# cs301_Group15.net
KiCad netlist of a schematic drawn in Altium Designer
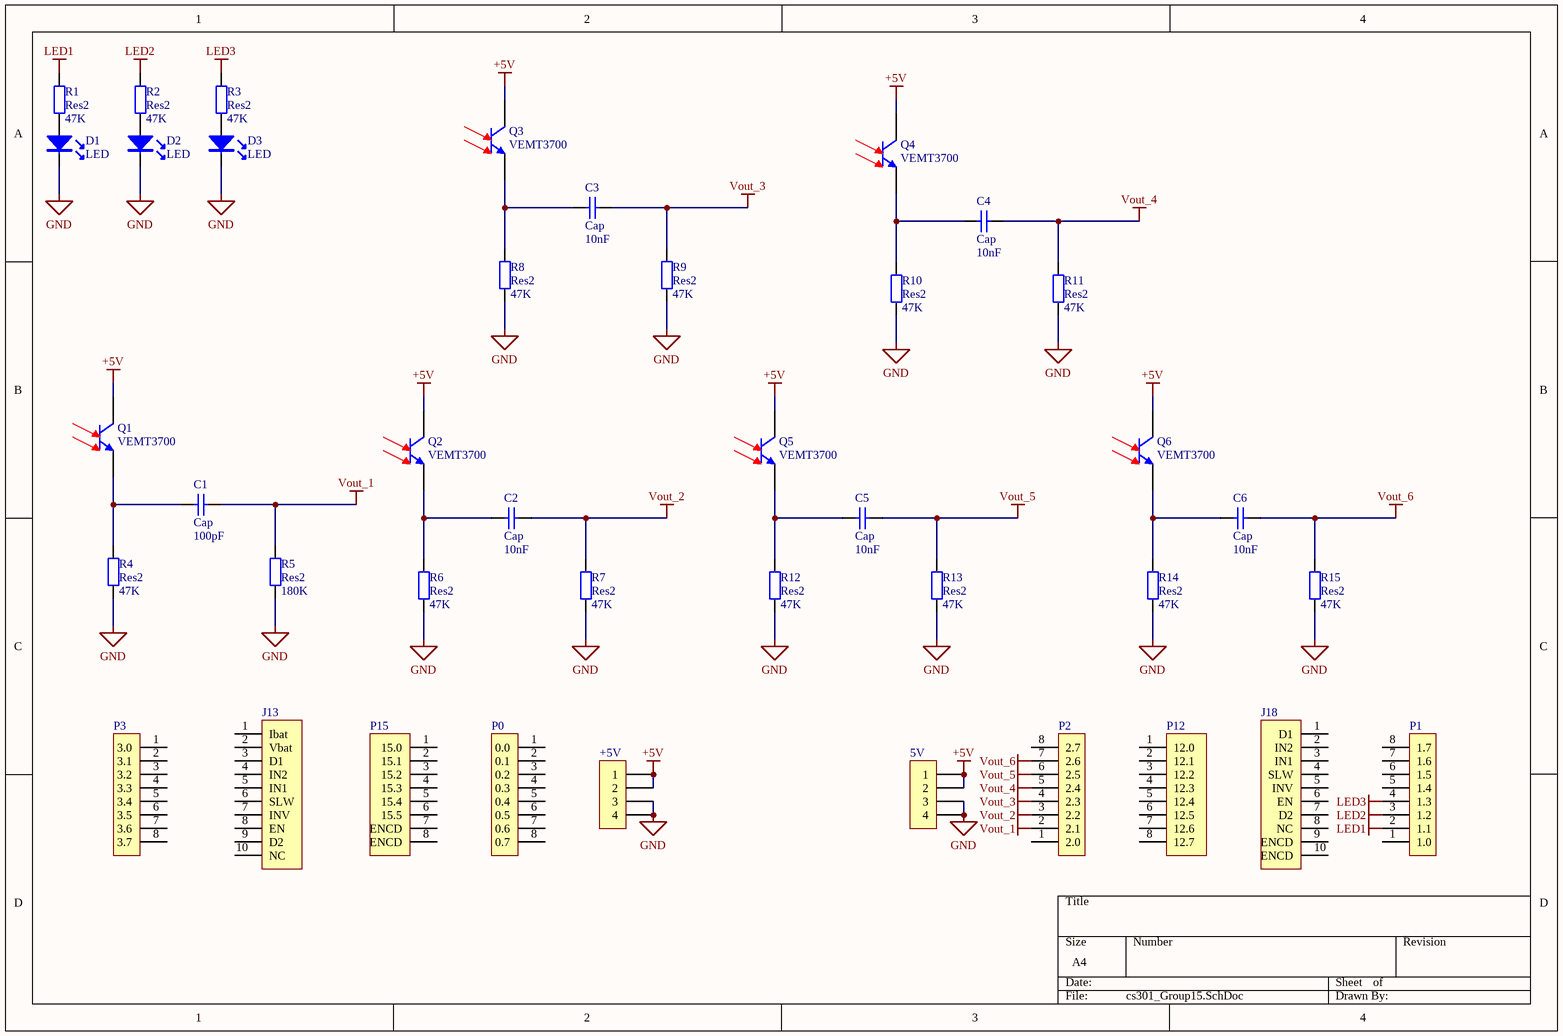
[diagram p0: cs301_Group15.SchDoc]

(export (version "E")
  (design (tool "Eeschema 10.0.6"))
  (components
    (comp (ref "+5V")
      (value "5V")
      (footprint "IDC4")
      (description "Connector")
      (libsource (lib "Miscellaneous Devices") (part "CON4"))
    )
    (comp (ref "5V")
      (value "5V")
      (footprint "IDC4")
      (description "Connector")
      (libsource (lib "Miscellaneous Devices") (part "CON4"))
    )
    (comp (ref "C1")
      (value "Cap")
      (footprint "RAD-0.3")
      (description "Capacitor")
      (fields (field (name "ALTIUM_VALUE") "100pF") (field (name "PUBLISHER") "Altium Limited"))
      (libsource (lib "Miscellaneous Devices") (part "Cap"))
    )
    (comp (ref "C2")
      (value "Cap")
      (footprint "RAD-0.3")
      (description "Capacitor")
      (fields (field (name "ALTIUM_VALUE") "10nF") (field (name "PUBLISHER") "Altium Limited"))
      (libsource (lib "Miscellaneous Devices") (part "Cap"))
    )
    (comp (ref "C3")
      (value "Cap")
      (footprint "RAD-0.3")
      (description "Capacitor")
      (fields (field (name "ALTIUM_VALUE") "10nF") (field (name "PUBLISHER") "Altium Limited"))
      (libsource (lib "Miscellaneous Devices") (part "Cap"))
    )
    (comp (ref "C4")
      (value "Cap")
      (footprint "RAD-0.3")
      (description "Capacitor")
      (fields (field (name "ALTIUM_VALUE") "10nF") (field (name "PUBLISHER") "Altium Limited"))
      (libsource (lib "Miscellaneous Devices") (part "Cap"))
    )
    (comp (ref "C5")
      (value "Cap")
      (footprint "RAD-0.3")
      (description "Capacitor")
      (fields (field (name "ALTIUM_VALUE") "10nF") (field (name "PUBLISHER") "Altium Limited"))
      (libsource (lib "Miscellaneous Devices") (part "Cap"))
    )
    (comp (ref "C6")
      (value "Cap")
      (footprint "RAD-0.3")
      (description "Capacitor")
      (fields (field (name "ALTIUM_VALUE") "10nF") (field (name "PUBLISHER") "Altium Limited"))
      (libsource (lib "Miscellaneous Devices") (part "Cap"))
    )
    (comp (ref "D1") (value "LED") (footprint "LED0.1/5MM") (libsource (lib "COMSYS301_2013") (part "LED")))
    (comp (ref "D2") (value "LED") (footprint "LED0.1/5MM") (libsource (lib "COMSYS301_2013") (part "LED")))
    (comp (ref "D3") (value "LED") (footprint "LED0.1/5MM") (libsource (lib "COMSYS301_2013") (part "LED")))
    (comp (ref "J13")
      (value "CON10")
      (footprint "idc10")
      (description "Connector")
      (libsource (lib "") (part "CON10_1"))
    )
    (comp (ref "J18")
      (value "CON10")
      (footprint "IDC10")
      (description "Connector")
      (libsource (lib "Miscellaneous Devices") (part "CON10"))
    )
    (comp (ref "P0")
      (value "P0")
      (footprint "idc8")
      (description "Connector")
      (libsource (lib "Miscellaneous Devices") (part "CON8"))
    )
    (comp (ref "P1")
      (value "P1")
      (footprint "idc8")
      (description "Connector")
      (libsource (lib "") (part "CON8_2"))
    )
    (comp (ref "P2")
      (value "P2")
      (footprint "idc8")
      (description "Connector")
      (libsource (lib "") (part "CON8_1"))
    )
    (comp (ref "P3")
      (value "P3")
      (footprint "idc8")
      (description "Connector")
      (libsource (lib "Miscellaneous Devices") (part "CON8"))
    )
    (comp (ref "P12")
      (value "P12")
      (footprint "idc8")
      (description "Connector")
      (libsource (lib "Miscellaneous Devices") (part "CON8_1"))
    )
    (comp (ref "P15")
      (value "P15")
      (footprint "idc8")
      (description "Connector")
      (libsource (lib "") (part "CON8_1_1"))
    )
    (comp (ref "Q1")
      (value "VEMT3700")
      (footprint "VEMT3700")
      (description "Silicon NPN Phototransistor")
      (libsource (lib "COMSYS301_2013") (part "VEMT3700"))
    )
    (comp (ref "Q2")
      (value "VEMT3700")
      (footprint "VEMT3700")
      (description "Silicon NPN Phototransistor")
      (libsource (lib "COMSYS301_2013") (part "VEMT3700"))
    )
    (comp (ref "Q3")
      (value "VEMT3700")
      (footprint "VEMT3700")
      (description "Silicon NPN Phototransistor")
      (libsource (lib "COMSYS301_2013") (part "VEMT3700"))
    )
    (comp (ref "Q4")
      (value "VEMT3700")
      (footprint "VEMT3700")
      (description "Silicon NPN Phototransistor")
      (libsource (lib "COMSYS301_2013") (part "VEMT3700"))
    )
    (comp (ref "Q5")
      (value "VEMT3700")
      (footprint "VEMT3700")
      (description "Silicon NPN Phototransistor")
      (libsource (lib "COMSYS301_2013") (part "VEMT3700"))
    )
    (comp (ref "Q6")
      (value "VEMT3700")
      (footprint "VEMT3700")
      (description "Silicon NPN Phototransistor")
      (libsource (lib "COMSYS301_2013") (part "VEMT3700"))
    )
    (comp (ref "R1")
      (value "Res2")
      (footprint "AXIAL-0.4")
      (description "Resistor")
      (fields (field (name "ALTIUM_VALUE") "47K") (field (name "PUBLISHER") "Altium Limited"))
      (libsource (lib "Miscellaneous Devices") (part "Res2"))
    )
    (comp (ref "R2")
      (value "Res2")
      (footprint "AXIAL-0.4")
      (description "Resistor")
      (fields (field (name "ALTIUM_VALUE") "47K") (field (name "PUBLISHER") "Altium Limited"))
      (libsource (lib "Miscellaneous Devices") (part "Res2"))
    )
    (comp (ref "R3")
      (value "Res2")
      (footprint "AXIAL-0.4")
      (description "Resistor")
      (fields (field (name "ALTIUM_VALUE") "47K") (field (name "PUBLISHER") "Altium Limited"))
      (libsource (lib "Miscellaneous Devices") (part "Res2"))
    )
    (comp (ref "R4")
      (value "Res2")
      (footprint "AXIAL-0.4")
      (description "Resistor")
      (fields (field (name "ALTIUM_VALUE") "47K") (field (name "PUBLISHER") "Altium Limited"))
      (libsource (lib "Miscellaneous Devices") (part "Res2"))
    )
    (comp (ref "R5")
      (value "Res2")
      (footprint "AXIAL-0.4")
      (description "Resistor")
      (fields (field (name "ALTIUM_VALUE") "180K") (field (name "PUBLISHER") "Altium Limited"))
      (libsource (lib "Miscellaneous Devices") (part "Res2"))
    )
    (comp (ref "R6")
      (value "Res2")
      (footprint "AXIAL-0.4")
      (description "Resistor")
      (fields (field (name "ALTIUM_VALUE") "47K") (field (name "PUBLISHER") "Altium Limited"))
      (libsource (lib "Miscellaneous Devices") (part "Res2"))
    )
    (comp (ref "R7")
      (value "Res2")
      (footprint "AXIAL-0.4")
      (description "Resistor")
      (fields (field (name "ALTIUM_VALUE") "47K") (field (name "PUBLISHER") "Altium Limited"))
      (libsource (lib "Miscellaneous Devices") (part "Res2"))
    )
    (comp (ref "R8")
      (value "Res2")
      (footprint "AXIAL-0.4")
      (description "Resistor")
      (fields (field (name "ALTIUM_VALUE") "47K") (field (name "PUBLISHER") "Altium Limited"))
      (libsource (lib "Miscellaneous Devices") (part "Res2"))
    )
    (comp (ref "R9")
      (value "Res2")
      (footprint "AXIAL-0.4")
      (description "Resistor")
      (fields (field (name "ALTIUM_VALUE") "47K") (field (name "PUBLISHER") "Altium Limited"))
      (libsource (lib "Miscellaneous Devices") (part "Res2"))
    )
    (comp (ref "R10")
      (value "Res2")
      (footprint "AXIAL-0.4")
      (description "Resistor")
      (fields (field (name "ALTIUM_VALUE") "47K") (field (name "PUBLISHER") "Altium Limited"))
      (libsource (lib "Miscellaneous Devices") (part "Res2"))
    )
    (comp (ref "R11")
      (value "Res2")
      (footprint "AXIAL-0.4")
      (description "Resistor")
      (fields (field (name "ALTIUM_VALUE") "47K") (field (name "PUBLISHER") "Altium Limited"))
      (libsource (lib "Miscellaneous Devices") (part "Res2"))
    )
    (comp (ref "R12")
      (value "Res2")
      (footprint "AXIAL-0.4")
      (description "Resistor")
      (fields (field (name "ALTIUM_VALUE") "47K") (field (name "PUBLISHER") "Altium Limited"))
      (libsource (lib "Miscellaneous Devices") (part "Res2"))
    )
    (comp (ref "R13")
      (value "Res2")
      (footprint "AXIAL-0.4")
      (description "Resistor")
      (fields (field (name "ALTIUM_VALUE") "47K") (field (name "PUBLISHER") "Altium Limited"))
      (libsource (lib "Miscellaneous Devices") (part "Res2"))
    )
    (comp (ref "R14")
      (value "Res2")
      (footprint "AXIAL-0.4")
      (description "Resistor")
      (fields (field (name "ALTIUM_VALUE") "47K") (field (name "PUBLISHER") "Altium Limited"))
      (libsource (lib "Miscellaneous Devices") (part "Res2"))
    )
    (comp (ref "R15")
      (value "Res2")
      (footprint "AXIAL-0.4")
      (description "Resistor")
      (fields (field (name "ALTIUM_VALUE") "47K") (field (name "PUBLISHER") "Altium Limited"))
      (libsource (lib "Miscellaneous Devices") (part "Res2"))
    )
  )
  (nets
    (net (code "1") (name "+5V") (class "Default")
      (node (ref "+5V") (pin "1") (pinfunction "1_1") (pintype "passive"))
      (node (ref "+5V") (pin "2") (pinfunction "2_2") (pintype "passive"))
      (node (ref "5V") (pin "1") (pinfunction "1_1") (pintype "passive"))
      (node (ref "5V") (pin "2") (pinfunction "2_2") (pintype "passive"))
      (node (ref "Q1") (pin "1") (pinfunction "C_1") (pintype "passive"))
      (node (ref "Q2") (pin "1") (pinfunction "C_1") (pintype "passive"))
      (node (ref "Q3") (pin "1") (pinfunction "C_1") (pintype "passive"))
      (node (ref "Q4") (pin "1") (pinfunction "C_1") (pintype "passive"))
      (node (ref "Q5") (pin "1") (pinfunction "C_1") (pintype "passive"))
      (node (ref "Q6") (pin "1") (pinfunction "C_1") (pintype "passive"))
    )
    (net (code "2") (name "GND") (class "Default")
      (node (ref "+5V") (pin "3") (pinfunction "3_3") (pintype "passive"))
      (node (ref "+5V") (pin "4") (pinfunction "4_4") (pintype "passive"))
      (node (ref "5V") (pin "3") (pinfunction "3_3") (pintype "passive"))
      (node (ref "5V") (pin "4") (pinfunction "4_4") (pintype "passive"))
      (node (ref "D1") (pin "K") (pinfunction "2_K") (pintype "passive"))
      (node (ref "D2") (pin "K") (pinfunction "2_K") (pintype "passive"))
      (node (ref "D3") (pin "K") (pinfunction "2_K") (pintype "passive"))
      (node (ref "R10") (pin "1") (pinfunction "1_1") (pintype "passive"))
      (node (ref "R11") (pin "1") (pinfunction "1_1") (pintype "passive"))
      (node (ref "R12") (pin "1") (pinfunction "1_1") (pintype "passive"))
      (node (ref "R13") (pin "1") (pinfunction "1_1") (pintype "passive"))
      (node (ref "R14") (pin "1") (pinfunction "1_1") (pintype "passive"))
      (node (ref "R15") (pin "1") (pinfunction "1_1") (pintype "passive"))
      (node (ref "R4") (pin "1") (pinfunction "1_1") (pintype "passive"))
      (node (ref "R5") (pin "1") (pinfunction "1_1") (pintype "passive"))
      (node (ref "R6") (pin "1") (pinfunction "1_1") (pintype "passive"))
      (node (ref "R7") (pin "1") (pinfunction "1_1") (pintype "passive"))
      (node (ref "R8") (pin "1") (pinfunction "1_1") (pintype "passive"))
      (node (ref "R9") (pin "1") (pinfunction "1_1") (pintype "passive"))
    )
    (net (code "3") (name "LED1") (class "Default")
      (node (ref "P1") (pin "2") (pinfunction "1.1_2") (pintype "passive"))
      (node (ref "R1") (pin "2") (pinfunction "2_2") (pintype "passive"))
    )
    (net (code "4") (name "LED2") (class "Default")
      (node (ref "P1") (pin "3") (pinfunction "1.2_3") (pintype "passive"))
      (node (ref "R2") (pin "2") (pinfunction "2_2") (pintype "passive"))
    )
    (net (code "5") (name "LED3") (class "Default")
      (node (ref "P1") (pin "4") (pinfunction "1.3_4") (pintype "passive"))
      (node (ref "R3") (pin "2") (pinfunction "2_2") (pintype "passive"))
    )
    (net (code "6") (name "Net-(D1-1)") (class "Default")
      (node (ref "D1") (pin "A") (pinfunction "1_A") (pintype "passive"))
      (node (ref "R1") (pin "1") (pinfunction "1_1") (pintype "passive"))
    )
    (net (code "7") (name "Net-(D2-1)") (class "Default")
      (node (ref "D2") (pin "A") (pinfunction "1_A") (pintype "passive"))
      (node (ref "R2") (pin "1") (pinfunction "1_1") (pintype "passive"))
    )
    (net (code "8") (name "Net-(D3-1)") (class "Default")
      (node (ref "D3") (pin "A") (pinfunction "1_A") (pintype "passive"))
      (node (ref "R3") (pin "1") (pinfunction "1_1") (pintype "passive"))
    )
    (net (code "9") (name "Net-(Q1-E)") (class "Default")
      (node (ref "C1") (pin "1") (pinfunction "1_1") (pintype "passive"))
      (node (ref "Q1") (pin "2") (pinfunction "E_2") (pintype "passive"))
      (node (ref "R4") (pin "2") (pinfunction "2_2") (pintype "passive"))
    )
    (net (code "10") (name "Net-(Q2-E)") (class "Default")
      (node (ref "C2") (pin "1") (pinfunction "1_1") (pintype "passive"))
      (node (ref "Q2") (pin "2") (pinfunction "E_2") (pintype "passive"))
      (node (ref "R6") (pin "2") (pinfunction "2_2") (pintype "passive"))
    )
    (net (code "11") (name "Net-(Q3-E)") (class "Default")
      (node (ref "C3") (pin "1") (pinfunction "1_1") (pintype "passive"))
      (node (ref "Q3") (pin "2") (pinfunction "E_2") (pintype "passive"))
      (node (ref "R8") (pin "2") (pinfunction "2_2") (pintype "passive"))
    )
    (net (code "12") (name "Net-(Q4-E)") (class "Default")
      (node (ref "C4") (pin "1") (pinfunction "1_1") (pintype "passive"))
      (node (ref "Q4") (pin "2") (pinfunction "E_2") (pintype "passive"))
      (node (ref "R10") (pin "2") (pinfunction "2_2") (pintype "passive"))
    )
    (net (code "13") (name "Net-(Q5-E)") (class "Default")
      (node (ref "C5") (pin "1") (pinfunction "1_1") (pintype "passive"))
      (node (ref "Q5") (pin "2") (pinfunction "E_2") (pintype "passive"))
      (node (ref "R12") (pin "2") (pinfunction "2_2") (pintype "passive"))
    )
    (net (code "14") (name "Net-(Q6-E)") (class "Default")
      (node (ref "C6") (pin "1") (pinfunction "1_1") (pintype "passive"))
      (node (ref "Q6") (pin "2") (pinfunction "E_2") (pintype "passive"))
      (node (ref "R14") (pin "2") (pinfunction "2_2") (pintype "passive"))
    )
    (net (code "15") (name "Vout_1") (class "Default")
      (node (ref "C1") (pin "2") (pinfunction "2_2") (pintype "passive"))
      (node (ref "P2") (pin "2") (pinfunction "2.1_2") (pintype "passive"))
      (node (ref "R5") (pin "2") (pinfunction "2_2") (pintype "passive"))
    )
    (net (code "16") (name "Vout_2") (class "Default")
      (node (ref "C2") (pin "2") (pinfunction "2_2") (pintype "passive"))
      (node (ref "P2") (pin "3") (pinfunction "2.2_3") (pintype "passive"))
      (node (ref "R7") (pin "2") (pinfunction "2_2") (pintype "passive"))
    )
    (net (code "17") (name "Vout_3") (class "Default")
      (node (ref "C3") (pin "2") (pinfunction "2_2") (pintype "passive"))
      (node (ref "P2") (pin "4") (pinfunction "2.3_4") (pintype "passive"))
      (node (ref "R9") (pin "2") (pinfunction "2_2") (pintype "passive"))
    )
    (net (code "18") (name "Vout_4") (class "Default")
      (node (ref "C4") (pin "2") (pinfunction "2_2") (pintype "passive"))
      (node (ref "P2") (pin "5") (pinfunction "2.4_5") (pintype "passive"))
      (node (ref "R11") (pin "2") (pinfunction "2_2") (pintype "passive"))
    )
    (net (code "19") (name "Vout_5") (class "Default")
      (node (ref "C5") (pin "2") (pinfunction "2_2") (pintype "passive"))
      (node (ref "P2") (pin "6") (pinfunction "2.5_6") (pintype "passive"))
      (node (ref "R13") (pin "2") (pinfunction "2_2") (pintype "passive"))
    )
    (net (code "20") (name "Vout_6") (class "Default")
      (node (ref "C6") (pin "2") (pinfunction "2_2") (pintype "passive"))
      (node (ref "P2") (pin "7") (pinfunction "2.6_7") (pintype "passive"))
      (node (ref "R15") (pin "2") (pinfunction "2_2") (pintype "passive"))
    )
    (net (code "21") (name "unconnected-(J13-D1-Pad3)") (class "Default")
      (node (ref "J13") (pin "3") (pinfunction "D1_3") (pintype "passive"))
    )
    (net (code "22") (name "unconnected-(J13-D2-Pad9)") (class "Default")
      (node (ref "J13") (pin "9") (pinfunction "D2_9") (pintype "passive"))
    )
    (net (code "23") (name "unconnected-(J13-EN-Pad8)") (class "Default")
      (node (ref "J13") (pin "8") (pinfunction "EN_8") (pintype "passive"))
    )
    (net (code "24") (name "unconnected-(J13-IN1-Pad5)") (class "Default")
      (node (ref "J13") (pin "5") (pinfunction "IN1_5") (pintype "passive"))
    )
    (net (code "25") (name "unconnected-(J13-IN2-Pad4)") (class "Default")
      (node (ref "J13") (pin "4") (pinfunction "IN2_4") (pintype "passive"))
    )
    (net (code "26") (name "unconnected-(J13-INV-Pad7)") (class "Default")
      (node (ref "J13") (pin "7") (pinfunction "INV_7") (pintype "passive"))
    )
    (net (code "27") (name "unconnected-(J13-Ibat-Pad1)") (class "Default")
      (node (ref "J13") (pin "1") (pinfunction "Ibat_1") (pintype "passive"))
    )
    (net (code "28") (name "unconnected-(J13-NC-Pad10)") (class "Default")
      (node (ref "J13") (pin "10") (pinfunction "NC_10") (pintype "passive"))
    )
    (net (code "29") (name "unconnected-(J13-SLW-Pad6)") (class "Default")
      (node (ref "J13") (pin "6") (pinfunction "SLW_6") (pintype "passive"))
    )
    (net (code "30") (name "unconnected-(J13-Vbat-Pad2)") (class "Default")
      (node (ref "J13") (pin "2") (pinfunction "Vbat_2") (pintype "passive"))
    )
    (net (code "31") (name "unconnected-(J18-D1-Pad1)") (class "Default")
      (node (ref "J18") (pin "1") (pinfunction "D1_1") (pintype "passive"))
    )
    (net (code "32") (name "unconnected-(J18-D2-Pad7)") (class "Default")
      (node (ref "J18") (pin "7") (pinfunction "D2_7") (pintype "passive"))
    )
    (net (code "33") (name "unconnected-(J18-EN-Pad6)") (class "Default")
      (node (ref "J18") (pin "6") (pinfunction "EN_6") (pintype "passive"))
    )
    (net (code "34") (name "unconnected-(J18-ENCD-Pad9)") (class "Default")
      (node (ref "J18") (pin "9") (pinfunction "ENCD_9") (pintype "passive"))
    )
    (net (code "35") (name "unconnected-(J18-ENCD-Pad10)") (class "Default")
      (node (ref "J18") (pin "10") (pinfunction "ENCD_10") (pintype "passive"))
    )
    (net (code "36") (name "unconnected-(J18-IN1-Pad3)") (class "Default")
      (node (ref "J18") (pin "3") (pinfunction "IN1_3") (pintype "passive"))
    )
    (net (code "37") (name "unconnected-(J18-IN2-Pad2)") (class "Default")
      (node (ref "J18") (pin "2") (pinfunction "IN2_2") (pintype "passive"))
    )
    (net (code "38") (name "unconnected-(J18-INV-Pad5)") (class "Default")
      (node (ref "J18") (pin "5") (pinfunction "INV_5") (pintype "passive"))
    )
    (net (code "39") (name "unconnected-(J18-NC-Pad8)") (class "Default")
      (node (ref "J18") (pin "8") (pinfunction "NC_8") (pintype "passive"))
    )
    (net (code "40") (name "unconnected-(J18-SLW-Pad4)") (class "Default")
      (node (ref "J18") (pin "4") (pinfunction "SLW_4") (pintype "passive"))
    )
    (net (code "41") (name "unconnected-(P0-3.0-Pad1)") (class "Default")
      (node (ref "P0") (pin "1") (pinfunction "3.0_1") (pintype "passive"))
    )
    (net (code "42") (name "unconnected-(P0-3.1-Pad2)") (class "Default")
      (node (ref "P0") (pin "2") (pinfunction "3.1_2") (pintype "passive"))
    )
    (net (code "43") (name "unconnected-(P0-3.2-Pad3)") (class "Default")
      (node (ref "P0") (pin "3") (pinfunction "3.2_3") (pintype "passive"))
    )
    (net (code "44") (name "unconnected-(P0-3.3-Pad4)") (class "Default")
      (node (ref "P0") (pin "4") (pinfunction "3.3_4") (pintype "passive"))
    )
    (net (code "45") (name "unconnected-(P0-3.4-Pad5)") (class "Default")
      (node (ref "P0") (pin "5") (pinfunction "3.4_5") (pintype "passive"))
    )
    (net (code "46") (name "unconnected-(P0-3.5-Pad6)") (class "Default")
      (node (ref "P0") (pin "6") (pinfunction "3.5_6") (pintype "passive"))
    )
    (net (code "47") (name "unconnected-(P0-3.6-Pad7)") (class "Default")
      (node (ref "P0") (pin "7") (pinfunction "3.6_7") (pintype "passive"))
    )
    (net (code "48") (name "unconnected-(P0-3.7-Pad8)") (class "Default")
      (node (ref "P0") (pin "8") (pinfunction "3.7_8") (pintype "passive"))
    )
    (net (code "49") (name "unconnected-(P1-1.0-Pad1)") (class "Default")
      (node (ref "P1") (pin "1") (pinfunction "1.0_1") (pintype "passive"))
    )
    (net (code "50") (name "unconnected-(P1-1.4-Pad5)") (class "Default")
      (node (ref "P1") (pin "5") (pinfunction "1.4_5") (pintype "passive"))
    )
    (net (code "51") (name "unconnected-(P1-1.5-Pad6)") (class "Default")
      (node (ref "P1") (pin "6") (pinfunction "1.5_6") (pintype "passive"))
    )
    (net (code "52") (name "unconnected-(P1-1.6-Pad7)") (class "Default")
      (node (ref "P1") (pin "7") (pinfunction "1.6_7") (pintype "passive"))
    )
    (net (code "53") (name "unconnected-(P1-1.7-Pad8)") (class "Default")
      (node (ref "P1") (pin "8") (pinfunction "1.7_8") (pintype "passive"))
    )
    (net (code "54") (name "unconnected-(P2-2.0-Pad1)") (class "Default")
      (node (ref "P2") (pin "1") (pinfunction "2.0_1") (pintype "passive"))
    )
    (net (code "55") (name "unconnected-(P2-2.7-Pad8)") (class "Default")
      (node (ref "P2") (pin "8") (pinfunction "2.7_8") (pintype "passive"))
    )
    (net (code "56") (name "unconnected-(P3-3.0-Pad1)") (class "Default")
      (node (ref "P3") (pin "1") (pinfunction "3.0_1") (pintype "passive"))
    )
    (net (code "57") (name "unconnected-(P3-3.1-Pad2)") (class "Default")
      (node (ref "P3") (pin "2") (pinfunction "3.1_2") (pintype "passive"))
    )
    (net (code "58") (name "unconnected-(P3-3.2-Pad3)") (class "Default")
      (node (ref "P3") (pin "3") (pinfunction "3.2_3") (pintype "passive"))
    )
    (net (code "59") (name "unconnected-(P3-3.3-Pad4)") (class "Default")
      (node (ref "P3") (pin "4") (pinfunction "3.3_4") (pintype "passive"))
    )
    (net (code "60") (name "unconnected-(P3-3.4-Pad5)") (class "Default")
      (node (ref "P3") (pin "5") (pinfunction "3.4_5") (pintype "passive"))
    )
    (net (code "61") (name "unconnected-(P3-3.5-Pad6)") (class "Default")
      (node (ref "P3") (pin "6") (pinfunction "3.5_6") (pintype "passive"))
    )
    (net (code "62") (name "unconnected-(P3-3.6-Pad7)") (class "Default")
      (node (ref "P3") (pin "7") (pinfunction "3.6_7") (pintype "passive"))
    )
    (net (code "63") (name "unconnected-(P3-3.7-Pad8)") (class "Default")
      (node (ref "P3") (pin "8") (pinfunction "3.7_8") (pintype "passive"))
    )
    (net (code "64") (name "unconnected-(P12-12.0-Pad1)") (class "Default")
      (node (ref "P12") (pin "1") (pinfunction "12.0_1") (pintype "passive"))
    )
    (net (code "65") (name "unconnected-(P12-12.1-Pad2)") (class "Default")
      (node (ref "P12") (pin "2") (pinfunction "12.1_2") (pintype "passive"))
    )
    (net (code "66") (name "unconnected-(P12-12.2-Pad3)") (class "Default")
      (node (ref "P12") (pin "3") (pinfunction "12.2_3") (pintype "passive"))
    )
    (net (code "67") (name "unconnected-(P12-12.3-Pad4)") (class "Default")
      (node (ref "P12") (pin "4") (pinfunction "12.3_4") (pintype "passive"))
    )
    (net (code "68") (name "unconnected-(P12-12.4-Pad5)") (class "Default")
      (node (ref "P12") (pin "5") (pinfunction "12.4_5") (pintype "passive"))
    )
    (net (code "69") (name "unconnected-(P12-12.5-Pad6)") (class "Default")
      (node (ref "P12") (pin "6") (pinfunction "12.5_6") (pintype "passive"))
    )
    (net (code "70") (name "unconnected-(P12-12.6-Pad7)") (class "Default")
      (node (ref "P12") (pin "7") (pinfunction "12.6_7") (pintype "passive"))
    )
    (net (code "71") (name "unconnected-(P12-12.7-Pad8)") (class "Default")
      (node (ref "P12") (pin "8") (pinfunction "12.7_8") (pintype "passive"))
    )
    (net (code "72") (name "unconnected-(P15-15.0-Pad1)") (class "Default")
      (node (ref "P15") (pin "1") (pinfunction "15.0_1") (pintype "passive"))
    )
    (net (code "73") (name "unconnected-(P15-15.1-Pad2)") (class "Default")
      (node (ref "P15") (pin "2") (pinfunction "15.1_2") (pintype "passive"))
    )
    (net (code "74") (name "unconnected-(P15-15.2-Pad3)") (class "Default")
      (node (ref "P15") (pin "3") (pinfunction "15.2_3") (pintype "passive"))
    )
    (net (code "75") (name "unconnected-(P15-15.3-Pad4)") (class "Default")
      (node (ref "P15") (pin "4") (pinfunction "15.3_4") (pintype "passive"))
    )
    (net (code "76") (name "unconnected-(P15-15.4-Pad5)") (class "Default")
      (node (ref "P15") (pin "5") (pinfunction "15.4_5") (pintype "passive"))
    )
    (net (code "77") (name "unconnected-(P15-15.5-Pad6)") (class "Default")
      (node (ref "P15") (pin "6") (pinfunction "15.5_6") (pintype "passive"))
    )
    (net (code "78") (name "unconnected-(P15-ENCD-Pad7)") (class "Default")
      (node (ref "P15") (pin "7") (pinfunction "ENCD_7") (pintype "passive"))
    )
    (net (code "79") (name "unconnected-(P15-ENCD-Pad8)") (class "Default")
      (node (ref "P15") (pin "8") (pinfunction "ENCD_8") (pintype "passive"))
    )
  )
)
